# Sensor_board.net
KiCad netlist of a schematic drawn in EAGLE
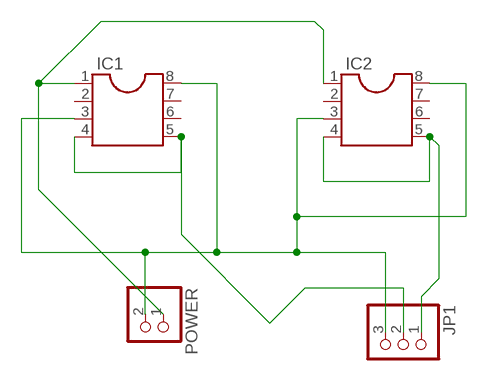
[diagram p0: schematic, sheet 1]

(export (version "E")
  (design (tool "Eeschema 10.0.6"))
  (components
    (comp (ref "IC1")
      (value "DIL8S")
      (footprint "eagle-import:SOCKET-08")
      (libsource (lib "eagle-import") (part "DIL8S"))
    )
    (comp (ref "IC2")
      (value "DIL8S")
      (footprint "eagle-import:SOCKET-08")
      (libsource (lib "eagle-import") (part "DIL8S"))
    )
    (comp (ref "JP1")
      (value "PINHD-1X3")
      (footprint "eagle-import:1X03")
      (libsource (lib "eagle-import") (part "PINHD-1X3"))
    )
    (comp (ref "POWER")
      (value "PINHD-1X2")
      (footprint "eagle-import:1X02")
      (libsource (lib "eagle-import") (part "PINHD-1X2"))
    )
  )
  (nets
    (net (code "1") (name "Net-(IC1-Pad1)") (class "Default")
      (node (ref "IC1") (pin "1") (pinfunction "1_1") (pintype "passive"))
      (node (ref "IC2") (pin "1") (pinfunction "1_1") (pintype "passive"))
      (node (ref "POWER") (pin "1") (pinfunction "1_1") (pintype "passive"))
    )
    (net (code "2") (name "Net-(IC1-Pad3)") (class "Default")
      (node (ref "IC1") (pin "3") (pinfunction "3_3") (pintype "passive"))
      (node (ref "IC1") (pin "8") (pinfunction "8_8") (pintype "passive"))
      (node (ref "IC2") (pin "3") (pinfunction "3_3") (pintype "passive"))
      (node (ref "IC2") (pin "8") (pinfunction "8_8") (pintype "passive"))
      (node (ref "JP1") (pin "3") (pinfunction "3_3") (pintype "passive"))
      (node (ref "POWER") (pin "2") (pinfunction "2_2") (pintype "passive"))
    )
    (net (code "3") (name "Net-(IC1-Pad4)") (class "Default")
      (node (ref "IC1") (pin "4") (pinfunction "4_4") (pintype "passive"))
      (node (ref "IC1") (pin "5") (pinfunction "5_5") (pintype "passive"))
      (node (ref "JP1") (pin "2") (pinfunction "2_2") (pintype "passive"))
    )
    (net (code "4") (name "Net-(IC2-Pad4)") (class "Default")
      (node (ref "IC2") (pin "4") (pinfunction "4_4") (pintype "passive"))
      (node (ref "IC2") (pin "5") (pinfunction "5_5") (pintype "passive"))
      (node (ref "JP1") (pin "1") (pinfunction "1_1") (pintype "passive"))
    )
    (net (code "5") (name "unconnected-(IC1-Pad2)") (class "Default")
      (node (ref "IC1") (pin "2") (pinfunction "2_2") (pintype "passive"))
    )
    (net (code "6") (name "unconnected-(IC1-Pad6)") (class "Default")
      (node (ref "IC1") (pin "6") (pinfunction "6_6") (pintype "passive"))
    )
    (net (code "7") (name "unconnected-(IC1-Pad7)") (class "Default")
      (node (ref "IC1") (pin "7") (pinfunction "7_7") (pintype "passive"))
    )
    (net (code "8") (name "unconnected-(IC2-Pad2)") (class "Default")
      (node (ref "IC2") (pin "2") (pinfunction "2_2") (pintype "passive"))
    )
    (net (code "9") (name "unconnected-(IC2-Pad6)") (class "Default")
      (node (ref "IC2") (pin "6") (pinfunction "6_6") (pintype "passive"))
    )
    (net (code "10") (name "unconnected-(IC2-Pad7)") (class "Default")
      (node (ref "IC2") (pin "7") (pinfunction "7_7") (pintype "passive"))
    )
  )
)
